# cpu_board.net
KiCad netlist of a schematic drawn in EAGLE
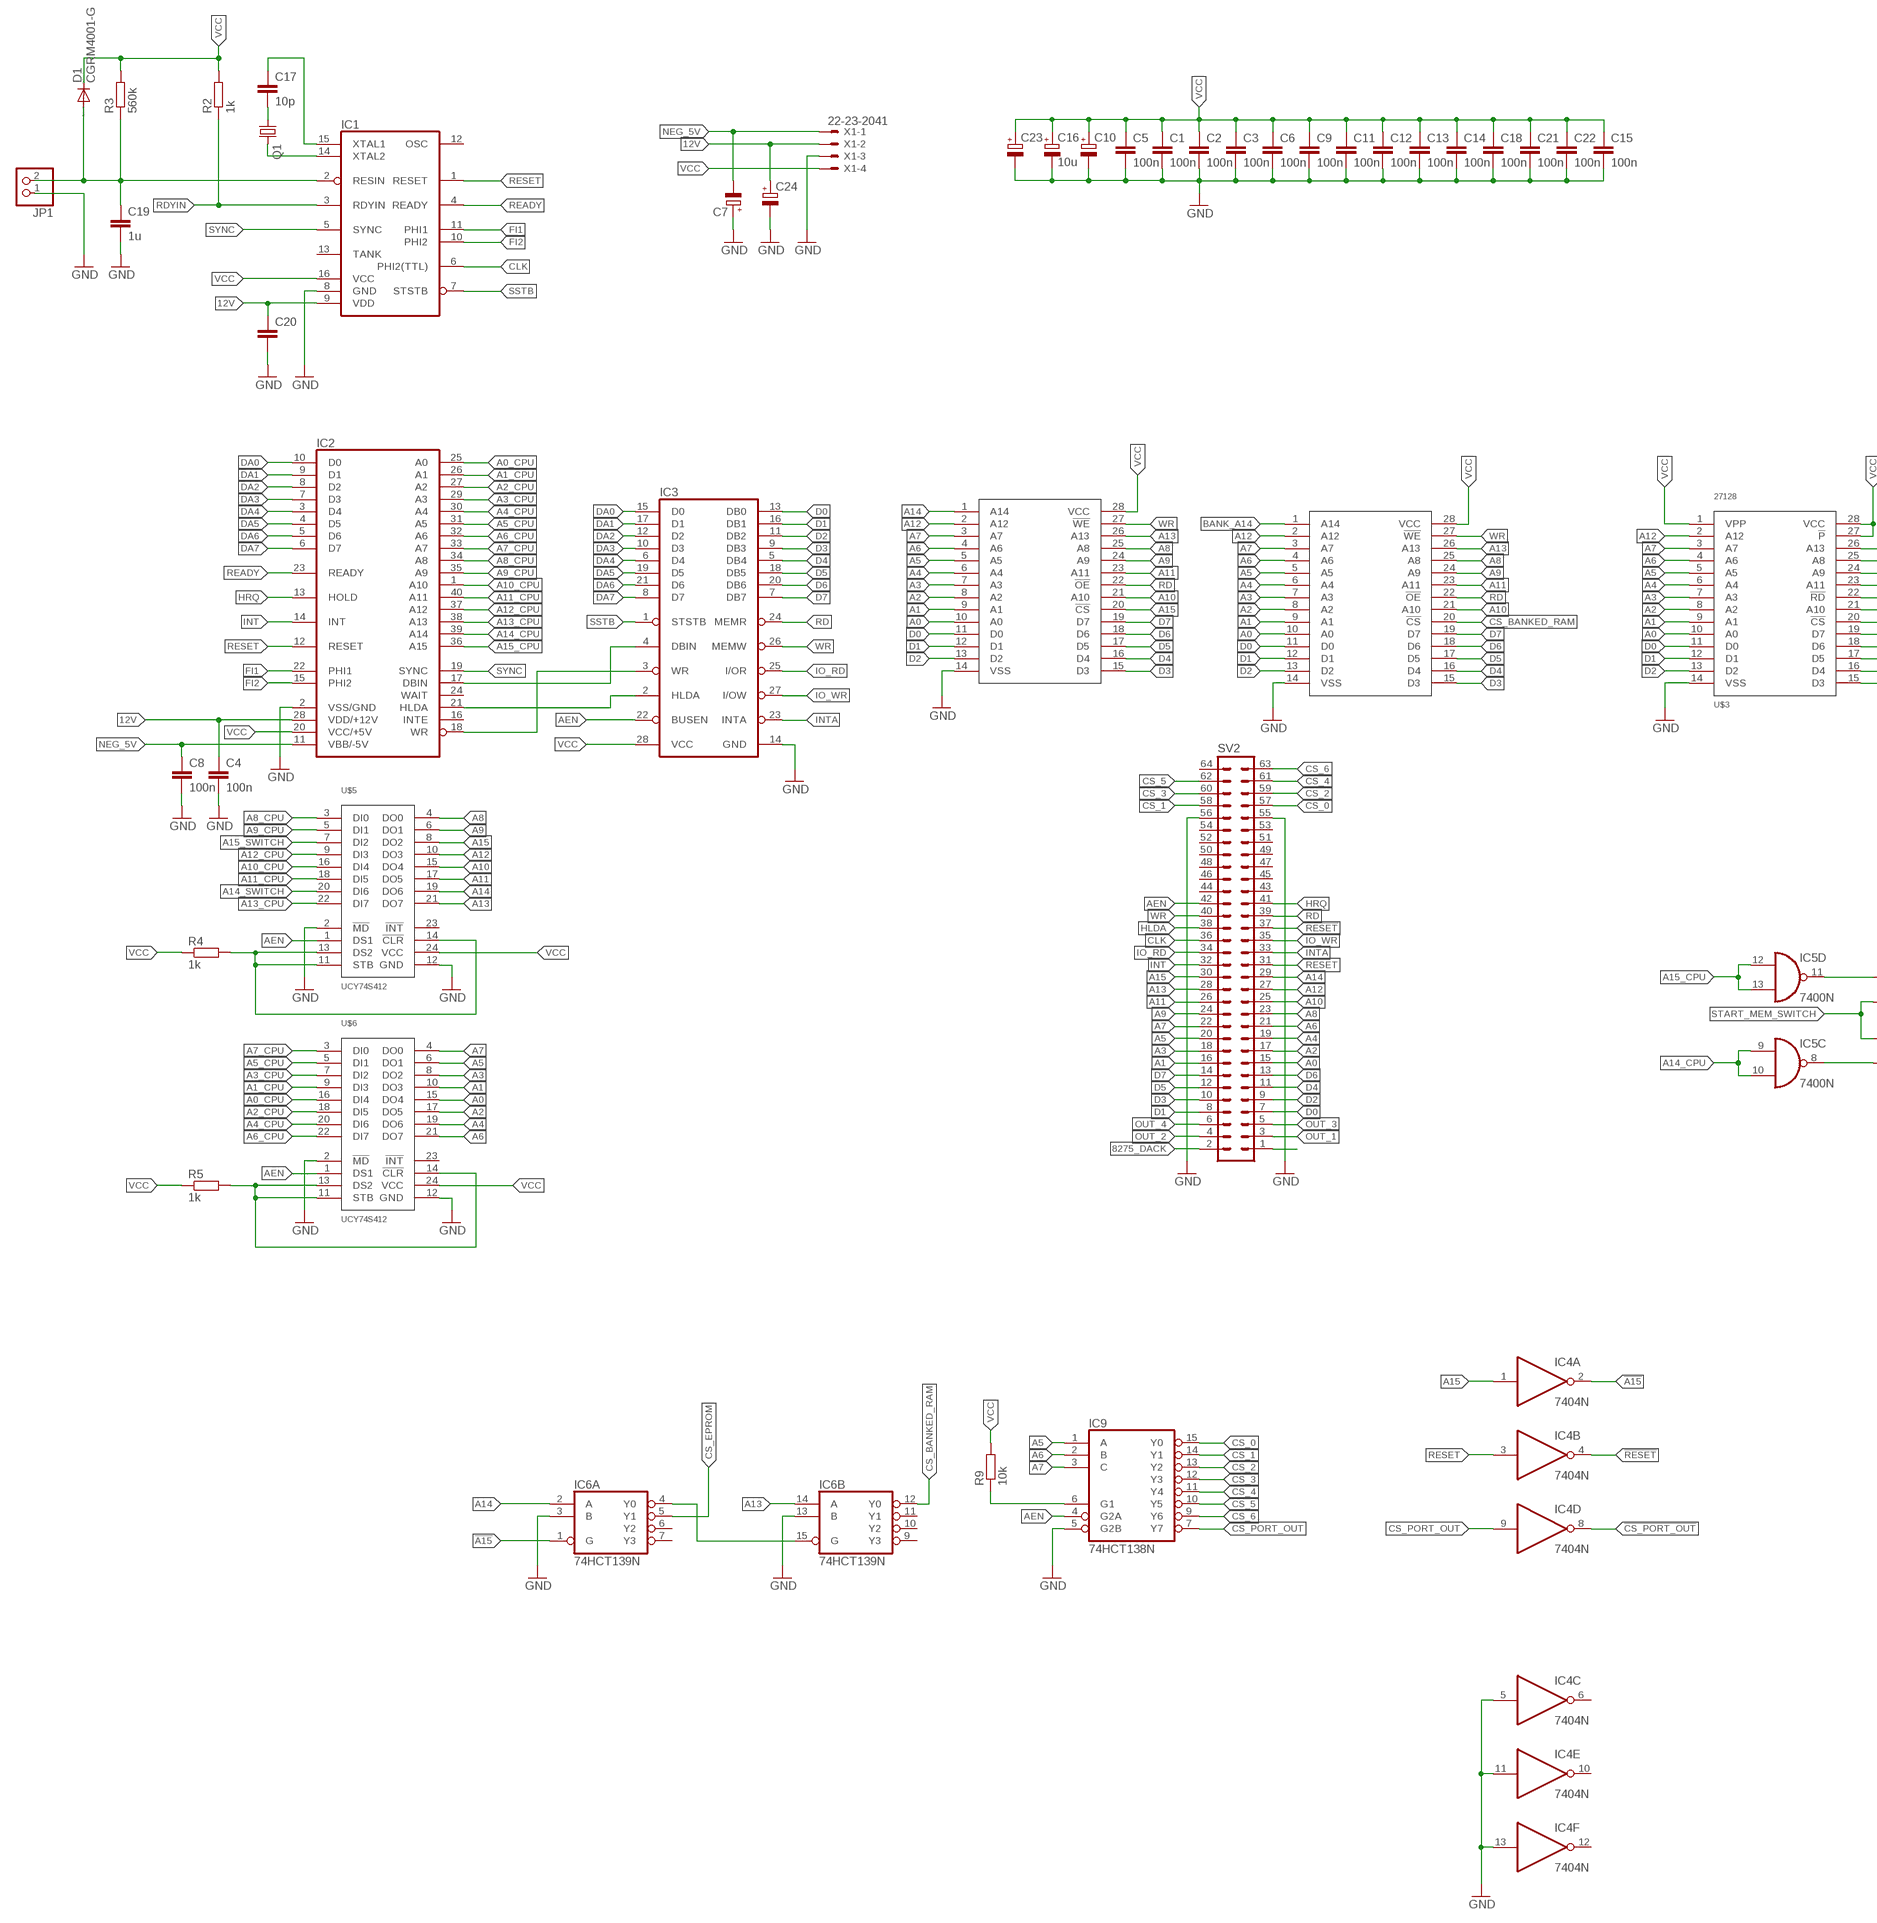
[diagram p0: schematic, sheet 1, part 1 of 2]
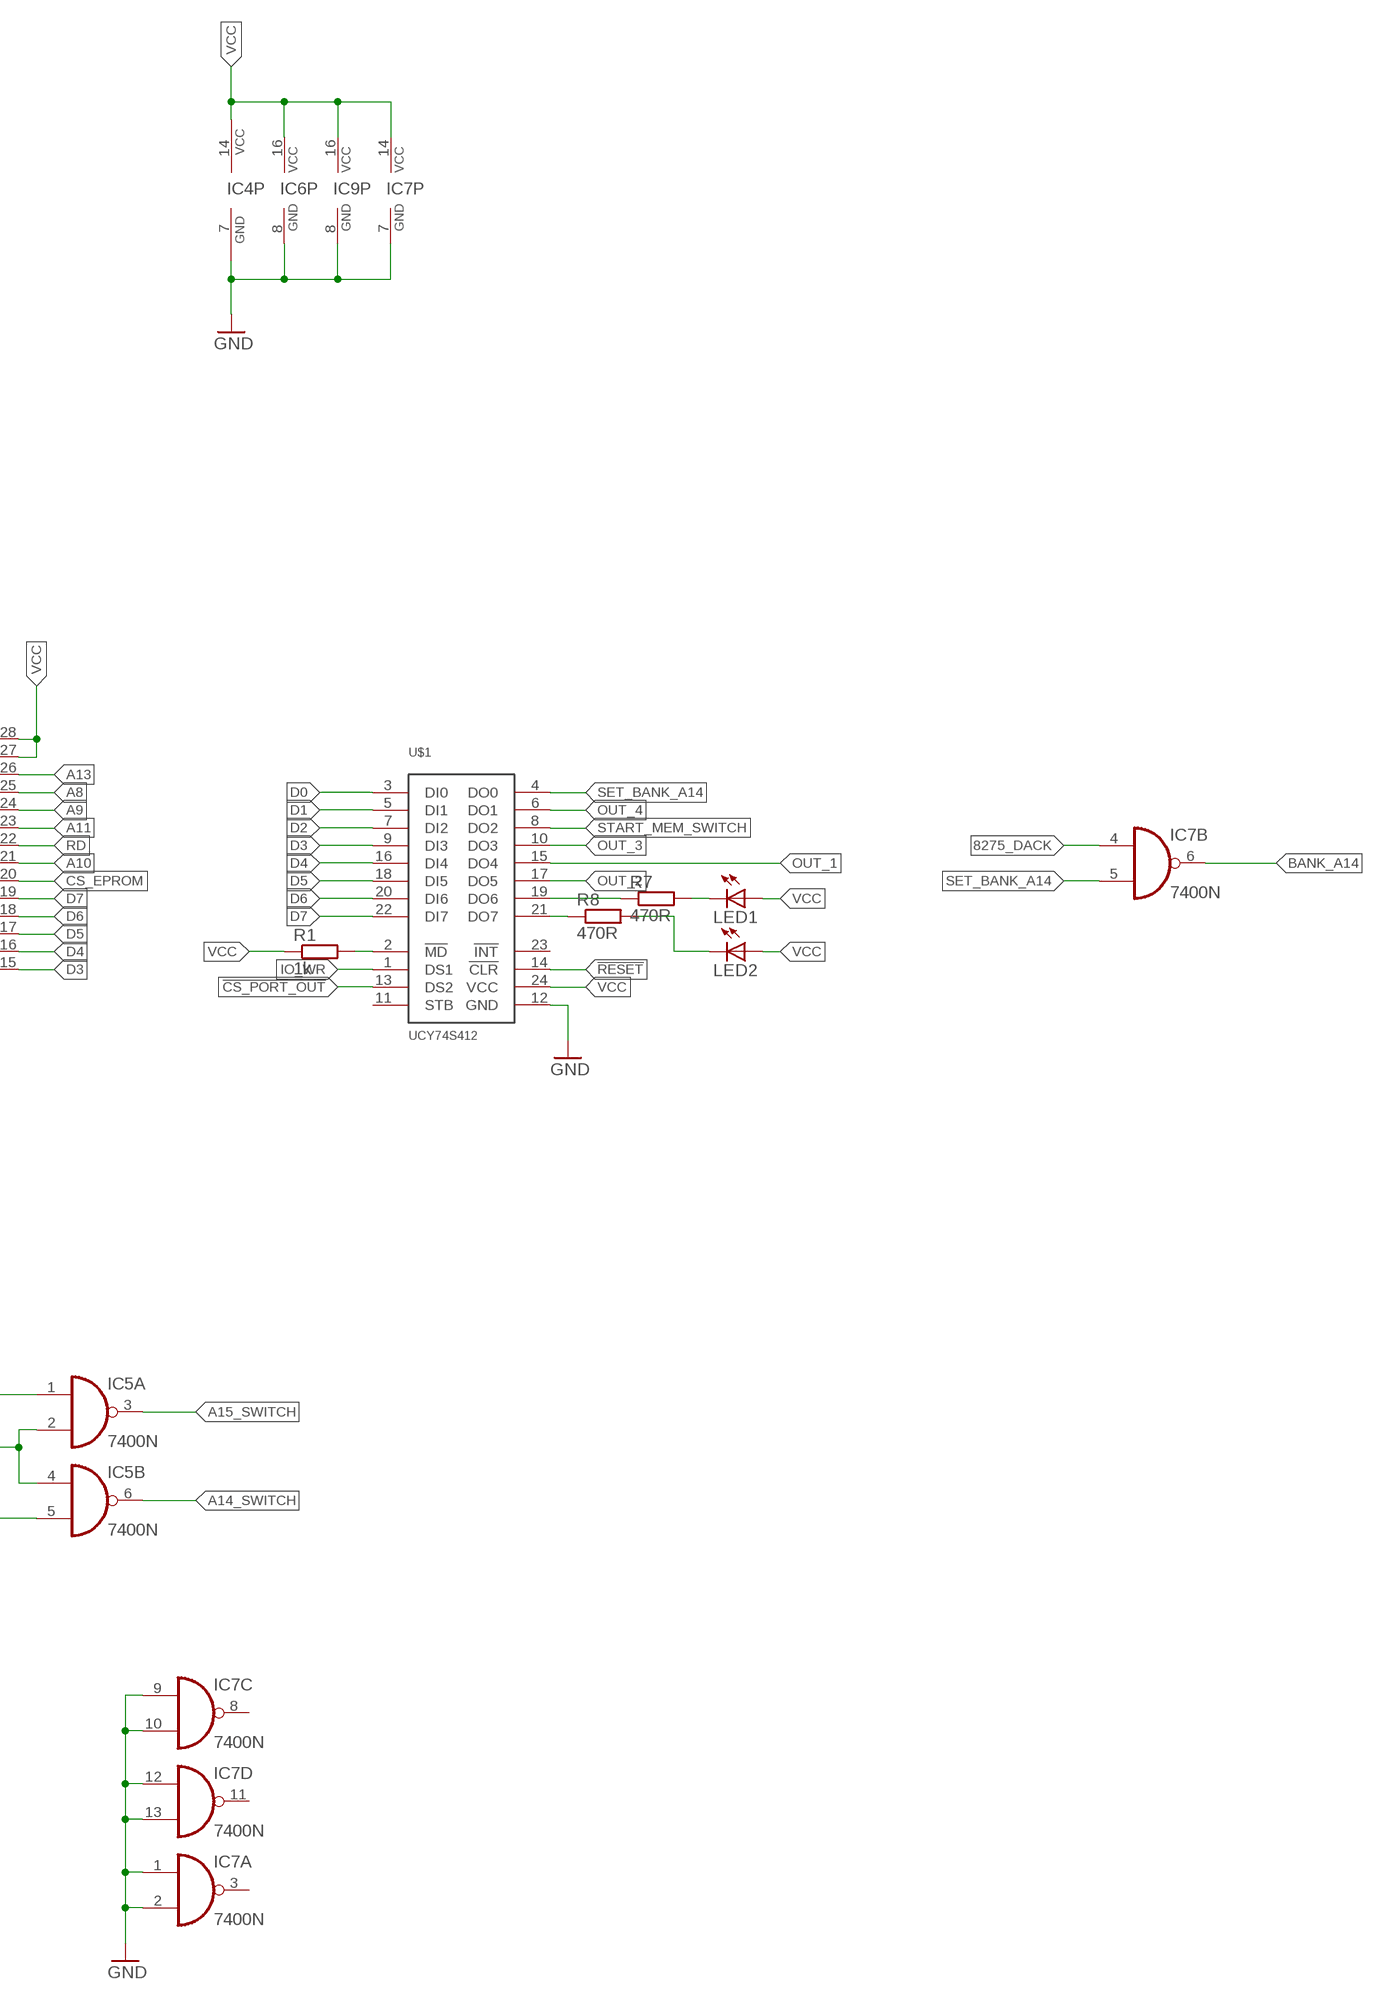
[diagram p1: schematic, sheet 1, part 2 of 2]

(export (version "E")
  (design (tool "Eeschema 10.0.6"))
  (components
    (comp (ref "C1")
      (value "100n")
      (footprint "eagle-import:C1206")
      (libsource (lib "eagle-import") (part "C-EUC1206"))
    )
    (comp (ref "C2")
      (value "100n")
      (footprint "eagle-import:C1206")
      (libsource (lib "eagle-import") (part "C-EUC1206"))
    )
    (comp (ref "C3")
      (value "100n")
      (footprint "eagle-import:C1206")
      (libsource (lib "eagle-import") (part "C-EUC1206"))
    )
    (comp (ref "C4")
      (value "100n")
      (footprint "eagle-import:C1206")
      (libsource (lib "eagle-import") (part "C-EUC1206"))
    )
    (comp (ref "C5")
      (value "100n")
      (footprint "eagle-import:C0603")
      (libsource (lib "eagle-import") (part "C-EUC0603"))
    )
    (comp (ref "C6")
      (value "100n")
      (footprint "eagle-import:C1206")
      (libsource (lib "eagle-import") (part "C-EUC1206"))
    )
    (comp (ref "C7")
      (value "CPOL-EUE2.5-7")
      (footprint "eagle-import:E2,5-7")
      (libsource (lib "eagle-import") (part "CPOL-EUE2.5-7"))
    )
    (comp (ref "C8")
      (value "100n")
      (footprint "eagle-import:C1206")
      (libsource (lib "eagle-import") (part "C-EUC1206"))
    )
    (comp (ref "C9")
      (value "100n")
      (footprint "eagle-import:C1206")
      (libsource (lib "eagle-import") (part "C-EUC1206"))
    )
    (comp (ref "C10")
      (value "CPOL-EUE5-10.5")
      (footprint "eagle-import:E5-10,5")
      (libsource (lib "eagle-import") (part "CPOL-EUE5-10.5"))
    )
    (comp (ref "C11")
      (value "100n")
      (footprint "eagle-import:C0805")
      (libsource (lib "eagle-import") (part "C-EUC0805"))
    )
    (comp (ref "C12")
      (value "100n")
      (footprint "eagle-import:C0805")
      (libsource (lib "eagle-import") (part "C-EUC0805"))
    )
    (comp (ref "C13")
      (value "100n")
      (footprint "eagle-import:C0805")
      (libsource (lib "eagle-import") (part "C-EUC0805"))
    )
    (comp (ref "C14")
      (value "100n")
      (footprint "eagle-import:C1206")
      (libsource (lib "eagle-import") (part "C-EUC1206"))
    )
    (comp (ref "C15")
      (value "100n")
      (footprint "eagle-import:C1206")
      (libsource (lib "eagle-import") (part "C-EUC1206"))
    )
    (comp (ref "C16")
      (value "10u")
      (footprint "eagle-import:SMC_B")
      (libsource (lib "eagle-import") (part "CPOL-EUSMCB"))
    )
    (comp (ref "C17")
      (value "10p")
      (footprint "eagle-import:C0603")
      (libsource (lib "eagle-import") (part "C-EUC0603"))
    )
    (comp (ref "C18")
      (value "100n")
      (footprint "eagle-import:C0603")
      (libsource (lib "eagle-import") (part "C-EUC0603"))
    )
    (comp (ref "C19")
      (value "1u")
      (footprint "eagle-import:C0603")
      (libsource (lib "eagle-import") (part "C-EUC0603"))
    )
    (comp (ref "C20")
      (value "C-EUC0603")
      (footprint "eagle-import:C0603")
      (libsource (lib "eagle-import") (part "C-EUC0603"))
    )
    (comp (ref "C21")
      (value "100n")
      (footprint "eagle-import:C1206")
      (libsource (lib "eagle-import") (part "C-EUC1206"))
    )
    (comp (ref "C22")
      (value "100n")
      (footprint "eagle-import:C0603")
      (libsource (lib "eagle-import") (part "C-EUC0603"))
    )
    (comp (ref "C23")
      (value "CPOL-EUE5-10.5")
      (footprint "eagle-import:E5-10,5")
      (libsource (lib "eagle-import") (part "CPOL-EUE5-10.5"))
    )
    (comp (ref "C24")
      (value "CPOL-EUE3.5-8")
      (footprint "eagle-import:E3,5-8")
      (libsource (lib "eagle-import") (part "CPOL-EUE3.5-8"))
    )
    (comp (ref "D1")
      (value "CGRM4001-G")
      (footprint "eagle-import:SOD-123_MINI-SMA")
      (libsource (lib "eagle-import") (part "CGRM400-G1"))
    )
    (comp (ref "IC1")
      (value "8224")
      (footprint "eagle-import:DIL16")
      (libsource (lib "eagle-import") (part "8224"))
    )
    (comp (ref "IC2")
      (value "8080")
      (footprint "eagle-import:DIL40")
      (libsource (lib "eagle-import") (part "8080"))
    )
    (comp (ref "IC3")
      (value "8228")
      (footprint "eagle-import:DIL28-6")
      (libsource (lib "eagle-import") (part "8228"))
    )
    (comp (ref "IC4")
      (value "7404N")
      (footprint "eagle-import:DIL14")
      (libsource (lib "eagle-import") (part "7404N"))
    )
    (comp (ref "IC5")
      (value "7400N")
      (footprint "eagle-import:DIL14")
      (libsource (lib "eagle-import") (part "7400N"))
    )
    (comp (ref "IC6")
      (value "74HCT139N")
      (footprint "eagle-import:DIL16")
      (libsource (lib "eagle-import") (part "74139NHCT"))
    )
    (comp (ref "IC7")
      (value "7400N")
      (footprint "eagle-import:DIL14")
      (libsource (lib "eagle-import") (part "7400N"))
    )
    (comp (ref "IC9")
      (value "74HCT138N")
      (footprint "eagle-import:DIL16")
      (libsource (lib "eagle-import") (part "74138NHCT"))
    )
    (comp (ref "JP1")
      (value "PINHD-1X2")
      (footprint "eagle-import:1X02")
      (libsource (lib "eagle-import") (part "PINHD-1X2"))
    )
    (comp (ref "LED1")
      (value "LED3MM")
      (footprint "eagle-import:LED3MM")
      (libsource (lib "eagle-import") (part "LED3MM"))
    )
    (comp (ref "LED2")
      (value "LED3MM")
      (footprint "eagle-import:LED3MM")
      (libsource (lib "eagle-import") (part "LED3MM"))
    )
    (comp (ref "Q1")
      (value "CRYSTALHC49U-V")
      (footprint "eagle-import:HC49U-V")
      (libsource (lib "eagle-import") (part "CRYSTALHC49U-V"))
    )
    (comp (ref "R1")
      (value "1k")
      (footprint "eagle-import:M1206")
      (libsource (lib "eagle-import") (part "R-EU_M1206"))
    )
    (comp (ref "R2")
      (value "1k")
      (footprint "eagle-import:R0603")
      (libsource (lib "eagle-import") (part "R-EU_R0603"))
    )
    (comp (ref "R3")
      (value "560k")
      (footprint "eagle-import:R0603")
      (libsource (lib "eagle-import") (part "R-EU_R0603"))
    )
    (comp (ref "R4")
      (value "1k")
      (footprint "eagle-import:R0603")
      (libsource (lib "eagle-import") (part "R-EU_R0603"))
    )
    (comp (ref "R5")
      (value "1k")
      (footprint "eagle-import:0204_7")
      (libsource (lib "eagle-import") (part "R-EU_0204/7"))
    )
    (comp (ref "R7")
      (value "470R")
      (footprint "eagle-import:R0603")
      (libsource (lib "eagle-import") (part "R-EU_R0603"))
    )
    (comp (ref "R8")
      (value "470R")
      (footprint "eagle-import:R0603")
      (libsource (lib "eagle-import") (part "R-EU_R0603"))
    )
    (comp (ref "R9")
      (value "10k")
      (footprint "eagle-import:R0603")
      (libsource (lib "eagle-import") (part "R-EU_R0603"))
    )
    (comp (ref "SV2")
      (value "ML64L")
      (footprint "eagle-import:ML64L")
      (libsource (lib "eagle-import") (part "ML64L"))
    )
    (comp (ref "U$1")
      (value "UCY74S412")
      (footprint "eagle-import:DIL24-6")
      (libsource (lib "eagle-import") (part "UCY74S412"))
    )
    (comp (ref "U$2")
      (value "62256")
      (footprint "eagle-import:DIL28-6")
      (libsource (lib "eagle-import") (part "62256"))
    )
    (comp (ref "U$3")
      (value "27128")
      (footprint "eagle-import:DIL28")
      (libsource (lib "eagle-import") (part "27128"))
    )
    (comp (ref "U$4")
      (value "62256")
      (footprint "eagle-import:DIL28-6")
      (libsource (lib "eagle-import") (part "62256"))
    )
    (comp (ref "U$5")
      (value "UCY74S412")
      (footprint "eagle-import:DIL24-6")
      (libsource (lib "eagle-import") (part "UCY74S412"))
    )
    (comp (ref "U$6")
      (value "UCY74S412")
      (footprint "eagle-import:DIL24-6")
      (libsource (lib "eagle-import") (part "UCY74S412"))
    )
    (comp (ref "X1")
      (value "22-23-2041")
      (footprint "eagle-import:22-23-2041")
      (fields (field (name "MF") "MOLEX"))
      (libsource (lib "eagle-import") (part "22-23-2041"))
    )
  )
  (nets
    (net (code "1") (name "/~{A15}") (class "Default")
      (node (ref "IC4") (pin "2") (pinfunction "O_2") (pintype "output"))
      (node (ref "IC6") (pin "1") (pinfunction "G_1") (pintype "input"))
    )
    (net (code "2") (name "/~{CS_PORT_OUT}") (class "Default")
      (node (ref "IC4") (pin "8") (pinfunction "O_8") (pintype "output"))
      (node (ref "U$1") (pin "13") (pinfunction "DS2_13") (pintype "bidirectional"))
    )
    (net (code "3") (name "/~{RESET}") (class "Default")
      (node (ref "IC4") (pin "4") (pinfunction "O_4") (pintype "output"))
      (node (ref "SV2") (pin "37") (pinfunction "37_37") (pintype "passive"))
      (node (ref "U$1") (pin "14") (pinfunction "~{CLR}_14") (pintype "bidirectional"))
    )
    (net (code "4") (name "12V") (class "Default")
      (node (ref "C20") (pin "1") (pinfunction "1_1") (pintype "passive"))
      (node (ref "C24") (pin "+") (pinfunction "+_+") (pintype "passive"))
      (node (ref "C4") (pin "1") (pinfunction "1_1") (pintype "passive"))
      (node (ref "IC1") (pin "9") (pinfunction "VDD_9") (pintype "power_in"))
      (node (ref "IC2") (pin "28") (pinfunction "VDD/+12V_28") (pintype "power_in"))
      (node (ref "X1") (pin "2") (pinfunction "S_2") (pintype "passive"))
    )
    (net (code "5") (name "8275_DACK") (class "Default")
      (node (ref "IC7") (pin "4") (pinfunction "I0_4") (pintype "input"))
      (node (ref "SV2") (pin "2") (pinfunction "2_2") (pintype "passive"))
    )
    (net (code "6") (name "A0") (class "Default")
      (node (ref "SV2") (pin "15") (pinfunction "15_15") (pintype "passive"))
      (node (ref "U$2") (pin "10") (pinfunction "A0_10") (pintype "bidirectional"))
      (node (ref "U$3") (pin "10") (pinfunction "A0_10") (pintype "bidirectional"))
      (node (ref "U$4") (pin "10") (pinfunction "A0_10") (pintype "bidirectional"))
      (node (ref "U$6") (pin "15") (pinfunction "DO4_15") (pintype "bidirectional"))
    )
    (net (code "7") (name "A0_CPU") (class "Default")
      (node (ref "IC2") (pin "25") (pinfunction "A0_25") (pintype "output"))
      (node (ref "U$6") (pin "16") (pinfunction "DI4_16") (pintype "bidirectional"))
    )
    (net (code "8") (name "A1") (class "Default")
      (node (ref "SV2") (pin "16") (pinfunction "16_16") (pintype "passive"))
      (node (ref "U$2") (pin "9") (pinfunction "A1_9") (pintype "bidirectional"))
      (node (ref "U$3") (pin "9") (pinfunction "A1_9") (pintype "bidirectional"))
      (node (ref "U$4") (pin "9") (pinfunction "A1_9") (pintype "bidirectional"))
      (node (ref "U$6") (pin "10") (pinfunction "DO3_10") (pintype "bidirectional"))
    )
    (net (code "9") (name "A1_CPU") (class "Default")
      (node (ref "IC2") (pin "26") (pinfunction "A1_26") (pintype "output"))
      (node (ref "U$6") (pin "9") (pinfunction "DI3_9") (pintype "bidirectional"))
    )
    (net (code "10") (name "A2") (class "Default")
      (node (ref "SV2") (pin "17") (pinfunction "17_17") (pintype "passive"))
      (node (ref "U$2") (pin "8") (pinfunction "A2_8") (pintype "bidirectional"))
      (node (ref "U$3") (pin "8") (pinfunction "A2_8") (pintype "bidirectional"))
      (node (ref "U$4") (pin "8") (pinfunction "A2_8") (pintype "bidirectional"))
      (node (ref "U$6") (pin "17") (pinfunction "DO5_17") (pintype "bidirectional"))
    )
    (net (code "11") (name "A2_CPU") (class "Default")
      (node (ref "IC2") (pin "27") (pinfunction "A2_27") (pintype "output"))
      (node (ref "U$6") (pin "18") (pinfunction "DI5_18") (pintype "bidirectional"))
    )
    (net (code "12") (name "A3") (class "Default")
      (node (ref "SV2") (pin "18") (pinfunction "18_18") (pintype "passive"))
      (node (ref "U$2") (pin "7") (pinfunction "A3_7") (pintype "bidirectional"))
      (node (ref "U$3") (pin "7") (pinfunction "A3_7") (pintype "bidirectional"))
      (node (ref "U$4") (pin "7") (pinfunction "A3_7") (pintype "bidirectional"))
      (node (ref "U$6") (pin "8") (pinfunction "DO2_8") (pintype "bidirectional"))
    )
    (net (code "13") (name "A3_CPU") (class "Default")
      (node (ref "IC2") (pin "29") (pinfunction "A3_29") (pintype "output"))
      (node (ref "U$6") (pin "7") (pinfunction "DI2_7") (pintype "bidirectional"))
    )
    (net (code "14") (name "A4") (class "Default")
      (node (ref "SV2") (pin "19") (pinfunction "19_19") (pintype "passive"))
      (node (ref "U$2") (pin "6") (pinfunction "A4_6") (pintype "bidirectional"))
      (node (ref "U$3") (pin "6") (pinfunction "A4_6") (pintype "bidirectional"))
      (node (ref "U$4") (pin "6") (pinfunction "A4_6") (pintype "bidirectional"))
      (node (ref "U$6") (pin "19") (pinfunction "DO6_19") (pintype "bidirectional"))
    )
    (net (code "15") (name "A4_CPU") (class "Default")
      (node (ref "IC2") (pin "30") (pinfunction "A4_30") (pintype "output"))
      (node (ref "U$6") (pin "20") (pinfunction "DI6_20") (pintype "bidirectional"))
    )
    (net (code "16") (name "A5") (class "Default")
      (node (ref "IC9") (pin "1") (pinfunction "A_1") (pintype "input"))
      (node (ref "SV2") (pin "20") (pinfunction "20_20") (pintype "passive"))
      (node (ref "U$2") (pin "5") (pinfunction "A5_5") (pintype "bidirectional"))
      (node (ref "U$3") (pin "5") (pinfunction "A5_5") (pintype "bidirectional"))
      (node (ref "U$4") (pin "5") (pinfunction "A5_5") (pintype "bidirectional"))
      (node (ref "U$6") (pin "6") (pinfunction "DO1_6") (pintype "bidirectional"))
    )
    (net (code "17") (name "A5_CPU") (class "Default")
      (node (ref "IC2") (pin "31") (pinfunction "A5_31") (pintype "output"))
      (node (ref "U$6") (pin "5") (pinfunction "DI1_5") (pintype "bidirectional"))
    )
    (net (code "18") (name "A6") (class "Default")
      (node (ref "IC9") (pin "2") (pinfunction "B_2") (pintype "input"))
      (node (ref "SV2") (pin "21") (pinfunction "21_21") (pintype "passive"))
      (node (ref "U$2") (pin "4") (pinfunction "A6_4") (pintype "bidirectional"))
      (node (ref "U$3") (pin "4") (pinfunction "A6_4") (pintype "bidirectional"))
      (node (ref "U$4") (pin "4") (pinfunction "A6_4") (pintype "bidirectional"))
      (node (ref "U$6") (pin "21") (pinfunction "DO7_21") (pintype "bidirectional"))
    )
    (net (code "19") (name "A6_CPU") (class "Default")
      (node (ref "IC2") (pin "32") (pinfunction "A6_32") (pintype "output"))
      (node (ref "U$6") (pin "22") (pinfunction "DI7_22") (pintype "bidirectional"))
    )
    (net (code "20") (name "A7") (class "Default")
      (node (ref "IC9") (pin "3") (pinfunction "C_3") (pintype "input"))
      (node (ref "SV2") (pin "22") (pinfunction "22_22") (pintype "passive"))
      (node (ref "U$2") (pin "3") (pinfunction "A7_3") (pintype "bidirectional"))
      (node (ref "U$3") (pin "3") (pinfunction "A7_3") (pintype "bidirectional"))
      (node (ref "U$4") (pin "3") (pinfunction "A7_3") (pintype "bidirectional"))
      (node (ref "U$6") (pin "4") (pinfunction "DO0_4") (pintype "bidirectional"))
    )
    (net (code "21") (name "A7_CPU") (class "Default")
      (node (ref "IC2") (pin "33") (pinfunction "A7_33") (pintype "output"))
      (node (ref "U$6") (pin "3") (pinfunction "DI0_3") (pintype "bidirectional"))
    )
    (net (code "22") (name "A8") (class "Default")
      (node (ref "SV2") (pin "23") (pinfunction "23_23") (pintype "passive"))
      (node (ref "U$2") (pin "25") (pinfunction "A8_25") (pintype "bidirectional"))
      (node (ref "U$3") (pin "25") (pinfunction "A8_25") (pintype "bidirectional"))
      (node (ref "U$4") (pin "25") (pinfunction "A8_25") (pintype "bidirectional"))
      (node (ref "U$5") (pin "4") (pinfunction "DO0_4") (pintype "bidirectional"))
    )
    (net (code "23") (name "A8_CPU") (class "Default")
      (node (ref "IC2") (pin "34") (pinfunction "A8_34") (pintype "output"))
      (node (ref "U$5") (pin "3") (pinfunction "DI0_3") (pintype "bidirectional"))
    )
    (net (code "24") (name "A9") (class "Default")
      (node (ref "SV2") (pin "24") (pinfunction "24_24") (pintype "passive"))
      (node (ref "U$2") (pin "24") (pinfunction "A9_24") (pintype "bidirectional"))
      (node (ref "U$3") (pin "24") (pinfunction "A9_24") (pintype "bidirectional"))
      (node (ref "U$4") (pin "24") (pinfunction "A9_24") (pintype "bidirectional"))
      (node (ref "U$5") (pin "6") (pinfunction "DO1_6") (pintype "bidirectional"))
    )
    (net (code "25") (name "A9_CPU") (class "Default")
      (node (ref "IC2") (pin "35") (pinfunction "A9_35") (pintype "output"))
      (node (ref "U$5") (pin "5") (pinfunction "DI1_5") (pintype "bidirectional"))
    )
    (net (code "26") (name "A10") (class "Default")
      (node (ref "SV2") (pin "25") (pinfunction "25_25") (pintype "passive"))
      (node (ref "U$2") (pin "21") (pinfunction "A10_21") (pintype "bidirectional"))
      (node (ref "U$3") (pin "21") (pinfunction "A10_21") (pintype "bidirectional"))
      (node (ref "U$4") (pin "21") (pinfunction "A10_21") (pintype "bidirectional"))
      (node (ref "U$5") (pin "15") (pinfunction "DO4_15") (pintype "bidirectional"))
    )
    (net (code "27") (name "A10_CPU") (class "Default")
      (node (ref "IC2") (pin "1") (pinfunction "A10_1") (pintype "output"))
      (node (ref "U$5") (pin "16") (pinfunction "DI4_16") (pintype "bidirectional"))
    )
    (net (code "28") (name "A11") (class "Default")
      (node (ref "SV2") (pin "26") (pinfunction "26_26") (pintype "passive"))
      (node (ref "U$2") (pin "23") (pinfunction "A11_23") (pintype "bidirectional"))
      (node (ref "U$3") (pin "23") (pinfunction "A11_23") (pintype "bidirectional"))
      (node (ref "U$4") (pin "23") (pinfunction "A11_23") (pintype "bidirectional"))
      (node (ref "U$5") (pin "17") (pinfunction "DO5_17") (pintype "bidirectional"))
    )
    (net (code "29") (name "A11_CPU") (class "Default")
      (node (ref "IC2") (pin "40") (pinfunction "A11_40") (pintype "output"))
      (node (ref "U$5") (pin "18") (pinfunction "DI5_18") (pintype "bidirectional"))
    )
    (net (code "30") (name "A12") (class "Default")
      (node (ref "SV2") (pin "27") (pinfunction "27_27") (pintype "passive"))
      (node (ref "U$2") (pin "2") (pinfunction "A12_2") (pintype "bidirectional"))
      (node (ref "U$3") (pin "2") (pinfunction "A12_2") (pintype "bidirectional"))
      (node (ref "U$4") (pin "2") (pinfunction "A12_2") (pintype "bidirectional"))
      (node (ref "U$5") (pin "10") (pinfunction "DO3_10") (pintype "bidirectional"))
    )
    (net (code "31") (name "A12_CPU") (class "Default")
      (node (ref "IC2") (pin "37") (pinfunction "A12_37") (pintype "output"))
      (node (ref "U$5") (pin "9") (pinfunction "DI3_9") (pintype "bidirectional"))
    )
    (net (code "32") (name "A13") (class "Default")
      (node (ref "IC6") (pin "14") (pinfunction "A_14") (pintype "input"))
      (node (ref "SV2") (pin "28") (pinfunction "28_28") (pintype "passive"))
      (node (ref "U$2") (pin "26") (pinfunction "A13_26") (pintype "bidirectional"))
      (node (ref "U$3") (pin "26") (pinfunction "A13_26") (pintype "bidirectional"))
      (node (ref "U$4") (pin "26") (pinfunction "A13_26") (pintype "bidirectional"))
      (node (ref "U$5") (pin "21") (pinfunction "DO7_21") (pintype "bidirectional"))
    )
    (net (code "33") (name "A13_CPU") (class "Default")
      (node (ref "IC2") (pin "38") (pinfunction "A13_38") (pintype "output"))
      (node (ref "U$5") (pin "22") (pinfunction "DI7_22") (pintype "bidirectional"))
    )
    (net (code "34") (name "A14") (class "Default")
      (node (ref "IC6") (pin "2") (pinfunction "A_2") (pintype "input"))
      (node (ref "SV2") (pin "29") (pinfunction "29_29") (pintype "passive"))
      (node (ref "U$4") (pin "1") (pinfunction "A14_1") (pintype "bidirectional"))
      (node (ref "U$5") (pin "19") (pinfunction "DO6_19") (pintype "bidirectional"))
    )
    (net (code "35") (name "A14_CPU") (class "Default")
      (node (ref "IC2") (pin "39") (pinfunction "A14_39") (pintype "output"))
      (node (ref "IC5") (pin "10") (pinfunction "I1_10") (pintype "input"))
      (node (ref "IC5") (pin "9") (pinfunction "I0_9") (pintype "input"))
    )
    (net (code "36") (name "A14_SWITCH") (class "Default")
      (node (ref "IC5") (pin "6") (pinfunction "O_6") (pintype "output"))
      (node (ref "U$5") (pin "20") (pinfunction "DI6_20") (pintype "bidirectional"))
    )
    (net (code "37") (name "A15") (class "Default")
      (node (ref "IC4") (pin "1") (pinfunction "I_1") (pintype "input"))
      (node (ref "SV2") (pin "30") (pinfunction "30_30") (pintype "passive"))
      (node (ref "U$4") (pin "20") (pinfunction "~{CS}_20") (pintype "bidirectional"))
      (node (ref "U$5") (pin "8") (pinfunction "DO2_8") (pintype "bidirectional"))
    )
    (net (code "38") (name "A15_CPU") (class "Default")
      (node (ref "IC2") (pin "36") (pinfunction "A15_36") (pintype "output"))
      (node (ref "IC5") (pin "12") (pinfunction "I0_12") (pintype "input"))
      (node (ref "IC5") (pin "13") (pinfunction "I1_13") (pintype "input"))
    )
    (net (code "39") (name "A15_SWITCH") (class "Default")
      (node (ref "IC5") (pin "3") (pinfunction "O_3") (pintype "output"))
      (node (ref "U$5") (pin "7") (pinfunction "DI2_7") (pintype "bidirectional"))
    )
    (net (code "40") (name "AEN") (class "Default")
      (node (ref "IC3") (pin "22") (pinfunction "BUSEN_22") (pintype "input"))
      (node (ref "IC9") (pin "4") (pinfunction "G2A_4") (pintype "input"))
      (node (ref "SV2") (pin "42") (pinfunction "42_42") (pintype "passive"))
      (node (ref "U$5") (pin "1") (pinfunction "DS1_1") (pintype "bidirectional"))
      (node (ref "U$6") (pin "1") (pinfunction "DS1_1") (pintype "bidirectional"))
    )
    (net (code "41") (name "BANK_A14") (class "Default")
      (node (ref "IC7") (pin "6") (pinfunction "O_6") (pintype "output"))
      (node (ref "U$2") (pin "1") (pinfunction "A14_1") (pintype "bidirectional"))
    )
    (net (code "42") (name "CLK") (class "Default")
      (node (ref "IC1") (pin "6") (pinfunction "PHI2(TTL)_6") (pintype "output"))
      (node (ref "SV2") (pin "36") (pinfunction "36_36") (pintype "passive"))
    )
    (net (code "43") (name "CS_0") (class "Default")
      (node (ref "IC9") (pin "15") (pinfunction "Y0_15") (pintype "output"))
      (node (ref "SV2") (pin "57") (pinfunction "57_57") (pintype "passive"))
    )
    (net (code "44") (name "CS_1") (class "Default")
      (node (ref "IC9") (pin "14") (pinfunction "Y1_14") (pintype "output"))
      (node (ref "SV2") (pin "58") (pinfunction "58_58") (pintype "passive"))
    )
    (net (code "45") (name "CS_2") (class "Default")
      (node (ref "IC9") (pin "13") (pinfunction "Y2_13") (pintype "output"))
      (node (ref "SV2") (pin "59") (pinfunction "59_59") (pintype "passive"))
    )
    (net (code "46") (name "CS_3") (class "Default")
      (node (ref "IC9") (pin "12") (pinfunction "Y3_12") (pintype "output"))
      (node (ref "SV2") (pin "60") (pinfunction "60_60") (pintype "passive"))
    )
    (net (code "47") (name "CS_4") (class "Default")
      (node (ref "IC9") (pin "11") (pinfunction "Y4_11") (pintype "output"))
      (node (ref "SV2") (pin "61") (pinfunction "61_61") (pintype "passive"))
    )
    (net (code "48") (name "CS_5") (class "Default")
      (node (ref "IC9") (pin "10") (pinfunction "Y5_10") (pintype "output"))
      (node (ref "SV2") (pin "62") (pinfunction "62_62") (pintype "passive"))
    )
    (net (code "49") (name "CS_6") (class "Default")
      (node (ref "IC9") (pin "9") (pinfunction "Y6_9") (pintype "output"))
      (node (ref "SV2") (pin "63") (pinfunction "63_63") (pintype "passive"))
    )
    (net (code "50") (name "CS_BANKED_RAM") (class "Default")
      (node (ref "IC6") (pin "12") (pinfunction "Y0_12") (pintype "output"))
      (node (ref "U$2") (pin "20") (pinfunction "~{CS}_20") (pintype "bidirectional"))
    )
    (net (code "51") (name "CS_EPROM") (class "Default")
      (node (ref "IC6") (pin "5") (pinfunction "Y1_5") (pintype "output"))
      (node (ref "U$3") (pin "20") (pinfunction "~{CS}_20") (pintype "bidirectional"))
    )
    (net (code "52") (name "CS_PORT_OUT") (class "Default")
      (node (ref "IC4") (pin "9") (pinfunction "I_9") (pintype "input"))
      (node (ref "IC9") (pin "7") (pinfunction "Y7_7") (pintype "output"))
    )
    (net (code "53") (name "D0") (class "Default")
      (node (ref "IC3") (pin "13") (pinfunction "DB0_13") (pintype "bidirectional"))
      (node (ref "SV2") (pin "7") (pinfunction "7_7") (pintype "passive"))
      (node (ref "U$1") (pin "3") (pinfunction "DI0_3") (pintype "bidirectional"))
      (node (ref "U$2") (pin "11") (pinfunction "D0_11") (pintype "bidirectional"))
      (node (ref "U$3") (pin "11") (pinfunction "D0_11") (pintype "bidirectional"))
      (node (ref "U$4") (pin "11") (pinfunction "D0_11") (pintype "bidirectional"))
    )
    (net (code "54") (name "D1") (class "Default")
      (node (ref "IC3") (pin "16") (pinfunction "DB1_16") (pintype "bidirectional"))
      (node (ref "SV2") (pin "8") (pinfunction "8_8") (pintype "passive"))
      (node (ref "U$1") (pin "5") (pinfunction "DI1_5") (pintype "bidirectional"))
      (node (ref "U$2") (pin "12") (pinfunction "D1_12") (pintype "bidirectional"))
      (node (ref "U$3") (pin "12") (pinfunction "D1_12") (pintype "bidirectional"))
      (node (ref "U$4") (pin "12") (pinfunction "D1_12") (pintype "bidirectional"))
    )
    (net (code "55") (name "D2") (class "Default")
      (node (ref "IC3") (pin "11") (pinfunction "DB2_11") (pintype "bidirectional"))
      (node (ref "SV2") (pin "9") (pinfunction "9_9") (pintype "passive"))
      (node (ref "U$1") (pin "7") (pinfunction "DI2_7") (pintype "bidirectional"))
      (node (ref "U$2") (pin "13") (pinfunction "D2_13") (pintype "bidirectional"))
      (node (ref "U$3") (pin "13") (pinfunction "D2_13") (pintype "bidirectional"))
      (node (ref "U$4") (pin "13") (pinfunction "D2_13") (pintype "bidirectional"))
    )
    (net (code "56") (name "D3") (class "Default")
      (node (ref "IC3") (pin "9") (pinfunction "DB3_9") (pintype "bidirectional"))
      (node (ref "SV2") (pin "10") (pinfunction "10_10") (pintype "passive"))
      (node (ref "U$1") (pin "9") (pinfunction "DI3_9") (pintype "bidirectional"))
      (node (ref "U$2") (pin "15") (pinfunction "D3_15") (pintype "bidirectional"))
      (node (ref "U$3") (pin "15") (pinfunction "D3_15") (pintype "bidirectional"))
      (node (ref "U$4") (pin "15") (pinfunction "D3_15") (pintype "bidirectional"))
    )
    (net (code "57") (name "D4") (class "Default")
      (node (ref "IC3") (pin "5") (pinfunction "DB4_5") (pintype "bidirectional"))
      (node (ref "SV2") (pin "11") (pinfunction "11_11") (pintype "passive"))
      (node (ref "U$1") (pin "16") (pinfunction "DI4_16") (pintype "bidirectional"))
      (node (ref "U$2") (pin "16") (pinfunction "D4_16") (pintype "bidirectional"))
      (node (ref "U$3") (pin "16") (pinfunction "D4_16") (pintype "bidirectional"))
      (node (ref "U$4") (pin "16") (pinfunction "D4_16") (pintype "bidirectional"))
    )
    (net (code "58") (name "D5") (class "Default")
      (node (ref "IC3") (pin "18") (pinfunction "DB5_18") (pintype "bidirectional"))
      (node (ref "SV2") (pin "12") (pinfunction "12_12") (pintype "passive"))
      (node (ref "U$1") (pin "18") (pinfunction "DI5_18") (pintype "bidirectional"))
      (node (ref "U$2") (pin "17") (pinfunction "D5_17") (pintype "bidirectional"))
      (node (ref "U$3") (pin "17") (pinfunction "D5_17") (pintype "bidirectional"))
      (node (ref "U$4") (pin "17") (pinfunction "D5_17") (pintype "bidirectional"))
    )
    (net (code "59") (name "D6") (class "Default")
      (node (ref "IC3") (pin "20") (pinfunction "DB6_20") (pintype "bidirectional"))
      (node (ref "SV2") (pin "13") (pinfunction "13_13") (pintype "passive"))
      (node (ref "U$1") (pin "20") (pinfunction "DI6_20") (pintype "bidirectional"))
      (node (ref "U$2") (pin "18") (pinfunction "D6_18") (pintype "bidirectional"))
      (node (ref "U$3") (pin "18") (pinfunction "D6_18") (pintype "bidirectional"))
      (node (ref "U$4") (pin "18") (pinfunction "D6_18") (pintype "bidirectional"))
    )
    (net (code "60") (name "D7") (class "Default")
      (node (ref "IC3") (pin "7") (pinfunction "DB7_7") (pintype "bidirectional"))
      (node (ref "SV2") (pin "14") (pinfunction "14_14") (pintype "passive"))
      (node (ref "U$1") (pin "22") (pinfunction "DI7_22") (pintype "bidirectional"))
      (node (ref "U$2") (pin "19") (pinfunction "D7_19") (pintype "bidirectional"))
      (node (ref "U$3") (pin "19") (pinfunction "D7_19") (pintype "bidirectional"))
      (node (ref "U$4") (pin "19") (pinfunction "D7_19") (pintype "bidirectional"))
    )
    (net (code "61") (name "DA0") (class "Default")
      (node (ref "IC2") (pin "10") (pinfunction "D0_10") (pintype "bidirectional"))
      (node (ref "IC3") (pin "15") (pinfunction "D0_15") (pintype "bidirectional"))
    )
    (net (code "62") (name "DA1") (class "Default")
      (node (ref "IC2") (pin "9") (pinfunction "D1_9") (pintype "bidirectional"))
      (node (ref "IC3") (pin "17") (pinfunction "D1_17") (pintype "bidirectional"))
    )
    (net (code "63") (name "DA2") (class "Default")
      (node (ref "IC2") (pin "8") (pinfunction "D2_8") (pintype "bidirectional"))
      (node (ref "IC3") (pin "12") (pinfunction "D2_12") (pintype "bidirectional"))
    )
    (net (code "64") (name "DA3") (class "Default")
      (node (ref "IC2") (pin "7") (pinfunction "D3_7") (pintype "bidirectional"))
      (node (ref "IC3") (pin "10") (pinfunction "D3_10") (pintype "bidirectional"))
    )
    (net (code "65") (name "DA4") (class "Default")
      (node (ref "IC2") (pin "3") (pinfunction "D4_3") (pintype "bidirectional"))
      (node (ref "IC3") (pin "6") (pinfunction "D4_6") (pintype "bidirectional"))
    )
    (net (code "66") (name "DA5") (class "Default")
      (node (ref "IC2") (pin "4") (pinfunction "D5_4") (pintype "bidirectional"))
      (node (ref "IC3") (pin "19") (pinfunction "D5_19") (pintype "bidirectional"))
    )
    (net (code "67") (name "DA6") (class "Default")
      (node (ref "IC2") (pin "5") (pinfunction "D6_5") (pintype "bidirectional"))
      (node (ref "IC3") (pin "21") (pinfunction "D6_21") (pintype "bidirectional"))
    )
    (net (code "68") (name "DA7") (class "Default")
      (node (ref "IC2") (pin "6") (pinfunction "D7_6") (pintype "bidirectional"))
      (node (ref "IC3") (pin "8") (pinfunction "D7_8") (pintype "bidirectional"))
    )
    (net (code "69") (name "FI1") (class "Default")
      (node (ref "IC1") (pin "11") (pinfunction "PHI1_11") (pintype "output"))
      (node (ref "IC2") (pin "22") (pinfunction "PHI1_22") (pintype "input"))
    )
    (net (code "70") (name "FI2") (class "Default")
      (node (ref "IC1") (pin "10") (pinfunction "PHI2_10") (pintype "output"))
      (node (ref "IC2") (pin "15") (pinfunction "PHI2_15") (pintype "input"))
    )
    (net (code "71") (name "GND") (class "Default")
      (node (ref "C1") (pin "2") (pinfunction "2_2") (pintype "passive"))
      (node (ref "C10") (pin "-") (pinfunction "-_-") (pintype "passive"))
      (node (ref "C11") (pin "2") (pinfunction "2_2") (pintype "passive"))
      (node (ref "C12") (pin "2") (pinfunction "2_2") (pintype "passive"))
      (node (ref "C13") (pin "2") (pinfunction "2_2") (pintype "passive"))
      (node (ref "C14") (pin "2") (pinfunction "2_2") (pintype "passive"))
      (node (ref "C15") (pin "2") (pinfunction "2_2") (pintype "passive"))
      (node (ref "C16") (pin "-") (pinfunction "-_-") (pintype "passive"))
      (node (ref "C18") (pin "2") (pinfunction "2_2") (pintype "passive"))
      (node (ref "C19") (pin "2") (pinfunction "2_2") (pintype "passive"))
      (node (ref "C2") (pin "2") (pinfunction "2_2") (pintype "passive"))
      (node (ref "C20") (pin "2") (pinfunction "2_2") (pintype "passive"))
      (node (ref "C21") (pin "2") (pinfunction "2_2") (pintype "passive"))
      (node (ref "C22") (pin "2") (pinfunction "2_2") (pintype "passive"))
      (node (ref "C23") (pin "-") (pinfunction "-_-") (pintype "passive"))
      (node (ref "C24") (pin "-") (pinfunction "-_-") (pintype "passive"))
      (node (ref "C3") (pin "2") (pinfunction "2_2") (pintype "passive"))
      (node (ref "C4") (pin "2") (pinfunction "2_2") (pintype "passive"))
      (node (ref "C5") (pin "2") (pinfunction "2_2") (pintype "passive"))
      (node (ref "C6") (pin "2") (pinfunction "2_2") (pintype "passive"))
      (node (ref "C7") (pin "+") (pinfunction "+_+") (pintype "passive"))
      (node (ref "C8") (pin "2") (pinfunction "2_2") (pintype "passive"))
      (node (ref "C9") (pin "2") (pinfunction "2_2") (pintype "passive"))
      (node (ref "IC1") (pin "8") (pinfunction "GND_8") (pintype "power_in"))
      (node (ref "IC2") (pin "2") (pinfunction "VSS/GND_2") (pintype "power_in"))
      (node (ref "IC3") (pin "14") (pinfunction "GND_14") (pintype "power_in"))
      (node (ref "IC4") (pin "11") (pinfunction "I_11") (pintype "input"))
      (node (ref "IC4") (pin "13") (pinfunction "I_13") (pintype "input"))
      (node (ref "IC4") (pin "5") (pinfunction "I_5") (pintype "input"))
      (node (ref "IC4") (pin "7") (pinfunction "GND_7") (pintype "power_in"))
      (node (ref "IC6") (pin "13") (pinfunction "B_13") (pintype "input"))
      (node (ref "IC6") (pin "3") (pinfunction "B_3") (pintype "input"))
      (node (ref "IC6") (pin "8") (pinfunction "GND_8") (pintype "power_in"))
      (node (ref "IC7") (pin "1") (pinfunction "I0_1") (pintype "input"))
      (node (ref "IC7") (pin "10") (pinfunction "I1_10") (pintype "input"))
      (node (ref "IC7") (pin "12") (pinfunction "I0_12") (pintype "input"))
      (node (ref "IC7") (pin "13") (pinfunction "I1_13") (pintype "input"))
      (node (ref "IC7") (pin "2") (pinfunction "I1_2") (pintype "input"))
      (node (ref "IC7") (pin "7") (pinfunction "GND_7") (pintype "power_in"))
      (node (ref "IC7") (pin "9") (pinfunction "I0_9") (pintype "input"))
      (node (ref "IC9") (pin "5") (pinfunction "G2B_5") (pintype "input"))
      (node (ref "IC9") (pin "8") (pinfunction "GND_8") (pintype "power_in"))
      (node (ref "JP1") (pin "1") (pinfunction "1_1") (pintype "passive"))
      (node (ref "SV2") (pin "55") (pinfunction "55_55") (pintype "passive"))
      (node (ref "SV2") (pin "56") (pinfunction "56_56") (pintype "passive"))
      (node (ref "U$1") (pin "12") (pinfunction "GND_12") (pintype "bidirectional"))
      (node (ref "U$2") (pin "14") (pinfunction "VSS_14") (pintype "bidirectional"))
      (node (ref "U$3") (pin "14") (pinfunction "VSS_14") (pintype "bidirectional"))
      (node (ref "U$4") (pin "14") (pinfunction "VSS_14") (pintype "bidirectional"))
      (node (ref "U$5") (pin "12") (pinfunction "GND_12") (pintype "bidirectional"))
      (node (ref "U$5") (pin "2") (pinfunction "~{MD}_2") (pintype "bidirectional"))
      (node (ref "U$6") (pin "12") (pinfunction "GND_12") (pintype "bidirectional"))
      (node (ref "U$6") (pin "2") (pinfunction "~{MD}_2") (pintype "bidirectional"))
      (node (ref "X1") (pin "3") (pinfunction "S_3") (pintype "passive"))
    )
    (net (code "72") (name "HLDA") (class "Default")
      (node (ref "IC2") (pin "21") (pinfunction "HLDA_21") (pintype "output"))
      (node (ref "IC3") (pin "2") (pinfunction "HLDA_2") (pintype "input"))
      (node (ref "SV2") (pin "38") (pinfunction "38_38") (pintype "passive"))
    )
    (net (code "73") (name "HRQ") (class "Default")
      (node (ref "IC2") (pin "13") (pinfunction "HOLD_13") (pintype "input"))
      (node (ref "SV2") (pin "41") (pinfunction "41_41") (pintype "passive"))
    )
    (net (code "74") (name "INT") (class "Default")
      (node (ref "IC2") (pin "14") (pinfunction "INT_14") (pintype "input"))
      (node (ref "SV2") (pin "32") (pinfunction "32_32") (pintype "passive"))
    )
    (net (code "75") (name "INTA") (class "Default")
      (node (ref "IC3") (pin "23") (pinfunction "INTA_23") (pintype "output"))
      (node (ref "SV2") (pin "33") (pinfunction "33_33") (pintype "passive"))
    )
    (net (code "76") (name "IO_RD") (class "Default")
      (node (ref "IC3") (pin "25") (pinfunction "I/OR_25") (pintype "output"))
      (node (ref "SV2") (pin "34") (pinfunction "34_34") (pintype "passive"))
    )
    (net (code "77") (name "IO_WR") (class "Default")
      (node (ref "IC3") (pin "27") (pinfunction "I/OW_27") (pintype "output"))
      (node (ref "SV2") (pin "35") (pinfunction "35_35") (pintype "passive"))
      (node (ref "U$1") (pin "1") (pinfunction "DS1_1") (pintype "bidirectional"))
    )
    (net (code "78") (name "NEG_5V") (class "Default")
      (node (ref "C7") (pin "-") (pinfunction "-_-") (pintype "passive"))
      (node (ref "C8") (pin "1") (pinfunction "1_1") (pintype "passive"))
      (node (ref "IC2") (pin "11") (pinfunction "VBB/-5V_11") (pintype "power_in"))
      (node (ref "X1") (pin "1") (pinfunction "S_1") (pintype "passive"))
    )
    (net (code "79") (name "Net-(C17-Pad2)") (class "Default")
      (node (ref "C17") (pin "2") (pinfunction "2_2") (pintype "passive"))
      (node (ref "Q1") (pin "1") (pinfunction "1_1") (pintype "passive"))
    )
    (net (code "80") (name "Net-(IC1-RESIN)") (class "Default")
      (node (ref "C19") (pin "1") (pinfunction "1_1") (pintype "passive"))
      (node (ref "D1") (pin "A") (pinfunction "A_A") (pintype "passive"))
      (node (ref "IC1") (pin "2") (pinfunction "RESIN_2") (pintype "input"))
      (node (ref "JP1") (pin "2") (pinfunction "2_2") (pintype "passive"))
      (node (ref "R3") (pin "1") (pinfunction "1_1") (pintype "passive"))
    )
    (net (code "81") (name "Net-(IC1-XTAL1)") (class "Default")
      (node (ref "C17") (pin "1") (pinfunction "1_1") (pintype "passive"))
      (node (ref "IC1") (pin "15") (pinfunction "XTAL1_15") (pintype "input"))
    )
    (net (code "82") (name "Net-(IC1-XTAL2)") (class "Default")
      (node (ref "IC1") (pin "14") (pinfunction "XTAL2_14") (pintype "input"))
      (node (ref "Q1") (pin "2") (pinfunction "2_2") (pintype "passive"))
    )
    (net (code "83") (name "Net-(IC2-DBIN)") (class "Default")
      (node (ref "IC2") (pin "17") (pinfunction "DBIN_17") (pintype "output"))
      (node (ref "IC3") (pin "4") (pinfunction "DBIN_4") (pintype "input"))
    )
    (net (code "84") (name "Net-(IC2-WR)") (class "Default")
      (node (ref "IC2") (pin "18") (pinfunction "WR_18") (pintype "output"))
      (node (ref "IC3") (pin "3") (pinfunction "WR_3") (pintype "input"))
    )
    (net (code "85") (name "Net-(IC5A-I0)") (class "Default")
      (node (ref "IC5") (pin "1") (pinfunction "I0_1") (pintype "input"))
      (node (ref "IC5") (pin "11") (pinfunction "O_11") (pintype "output"))
    )
    (net (code "86") (name "Net-(IC5B-I1)") (class "Default")
      (node (ref "IC5") (pin "5") (pinfunction "I1_5") (pintype "input"))
      (node (ref "IC5") (pin "8") (pinfunction "O_8") (pintype "output"))
    )
    (net (code "87") (name "Net-(IC6A-Y0)") (class "Default")
      (node (ref "IC6") (pin "15") (pinfunction "G_15") (pintype "input"))
      (node (ref "IC6") (pin "4") (pinfunction "Y0_4") (pintype "output"))
    )
    (net (code "88") (name "Net-(IC9A-G1)") (class "Default")
      (node (ref "IC9") (pin "6") (pinfunction "G1_6") (pintype "input"))
      (node (ref "R9") (pin "1") (pinfunction "1_1") (pintype "passive"))
    )
    (net (code "89") (name "Net-(LED1-C)") (class "Default")
      (node (ref "LED1") (pin "K") (pinfunction "C_K") (pintype "passive"))
      (node (ref "R7") (pin "2") (pinfunction "2_2") (pintype "passive"))
    )
    (net (code "90") (name "Net-(LED2-C)") (class "Default")
      (node (ref "LED2") (pin "K") (pinfunction "C_K") (pintype "passive"))
      (node (ref "R8") (pin "2") (pinfunction "2_2") (pintype "passive"))
    )
    (net (code "91") (name "Net-(U$1-DO6)") (class "Default")
      (node (ref "R7") (pin "1") (pinfunction "1_1") (pintype "passive"))
      (node (ref "U$1") (pin "19") (pinfunction "DO6_19") (pintype "bidirectional"))
    )
    (net (code "92") (name "Net-(U$1-DO7)") (class "Default")
      (node (ref "R8") (pin "1") (pinfunction "1_1") (pintype "passive"))
      (node (ref "U$1") (pin "21") (pinfunction "DO7_21") (pintype "bidirectional"))
    )
    (net (code "93") (name "Net-(U$1-~{MD})") (class "Default")
      (node (ref "R1") (pin "2") (pinfunction "2_2") (pintype "passive"))
      (node (ref "U$1") (pin "2") (pinfunction "~{MD}_2") (pintype "bidirectional"))
    )
    (net (code "94") (name "Net-(U$5-DS2)") (class "Default")
      (node (ref "R4") (pin "2") (pinfunction "2_2") (pintype "passive"))
      (node (ref "U$5") (pin "11") (pinfunction "STB_11") (pintype "bidirectional"))
      (node (ref "U$5") (pin "13") (pinfunction "DS2_13") (pintype "bidirectional"))
      (node (ref "U$5") (pin "14") (pinfunction "~{CLR}_14") (pintype "bidirectional"))
    )
    (net (code "95") (name "Net-(U$6-DS2)") (class "Default")
      (node (ref "R5") (pin "2") (pinfunction "2_2") (pintype "passive"))
      (node (ref "U$6") (pin "11") (pinfunction "STB_11") (pintype "bidirectional"))
      (node (ref "U$6") (pin "13") (pinfunction "DS2_13") (pintype "bidirectional"))
      (node (ref "U$6") (pin "14") (pinfunction "~{CLR}_14") (pintype "bidirectional"))
    )
    (net (code "96") (name "OUT_1") (class "Default")
      (node (ref "SV2") (pin "3") (pinfunction "3_3") (pintype "passive"))
      (node (ref "U$1") (pin "15") (pinfunction "DO4_15") (pintype "bidirectional"))
    )
    (net (code "97") (name "OUT_2") (class "Default")
      (node (ref "SV2") (pin "4") (pinfunction "4_4") (pintype "passive"))
      (node (ref "U$1") (pin "17") (pinfunction "DO5_17") (pintype "bidirectional"))
    )
    (net (code "98") (name "OUT_3") (class "Default")
      (node (ref "SV2") (pin "5") (pinfunction "5_5") (pintype "passive"))
      (node (ref "U$1") (pin "10") (pinfunction "DO3_10") (pintype "bidirectional"))
    )
    (net (code "99") (name "OUT_4") (class "Default")
      (node (ref "SV2") (pin "6") (pinfunction "6_6") (pintype "passive"))
      (node (ref "U$1") (pin "6") (pinfunction "DO1_6") (pintype "bidirectional"))
    )
    (net (code "100") (name "RD") (class "Default")
      (node (ref "IC3") (pin "24") (pinfunction "MEMR_24") (pintype "output"))
      (node (ref "SV2") (pin "39") (pinfunction "39_39") (pintype "passive"))
      (node (ref "U$2") (pin "22") (pinfunction "~{OE}_22") (pintype "bidirectional"))
      (node (ref "U$3") (pin "22") (pinfunction "~{RD}_22") (pintype "bidirectional"))
      (node (ref "U$4") (pin "22") (pinfunction "~{OE}_22") (pintype "bidirectional"))
    )
    (net (code "101") (name "RDYIN") (class "Default")
      (node (ref "IC1") (pin "3") (pinfunction "RDYIN_3") (pintype "input"))
      (node (ref "R2") (pin "1") (pinfunction "1_1") (pintype "passive"))
      (node (ref "SV2") (pin "1") (pinfunction "1_1") (pintype "passive"))
    )
    (net (code "102") (name "READY") (class "Default")
      (node (ref "IC1") (pin "4") (pinfunction "READY_4") (pintype "output"))
      (node (ref "IC2") (pin "23") (pinfunction "READY_23") (pintype "input"))
    )
    (net (code "103") (name "RESET") (class "Default")
      (node (ref "IC1") (pin "1") (pinfunction "RESET_1") (pintype "output"))
      (node (ref "IC2") (pin "12") (pinfunction "RESET_12") (pintype "input"))
      (node (ref "IC4") (pin "3") (pinfunction "I_3") (pintype "input"))
      (node (ref "SV2") (pin "31") (pinfunction "31_31") (pintype "passive"))
    )
    (net (code "104") (name "SET_BANK_A14") (class "Default")
      (node (ref "IC7") (pin "5") (pinfunction "I1_5") (pintype "input"))
      (node (ref "U$1") (pin "4") (pinfunction "DO0_4") (pintype "bidirectional"))
    )
    (net (code "105") (name "SSTB") (class "Default")
      (node (ref "IC1") (pin "7") (pinfunction "STSTB_7") (pintype "output"))
      (node (ref "IC3") (pin "1") (pinfunction "STSTB_1") (pintype "input"))
    )
    (net (code "106") (name "START_MEM_SWITCH") (class "Default")
      (node (ref "IC5") (pin "2") (pinfunction "I1_2") (pintype "input"))
      (node (ref "IC5") (pin "4") (pinfunction "I0_4") (pintype "input"))
      (node (ref "U$1") (pin "8") (pinfunction "DO2_8") (pintype "bidirectional"))
    )
    (net (code "107") (name "SYNC") (class "Default")
      (node (ref "IC1") (pin "5") (pinfunction "SYNC_5") (pintype "input"))
      (node (ref "IC2") (pin "19") (pinfunction "SYNC_19") (pintype "output"))
    )
    (net (code "108") (name "VCC") (class "Default")
      (node (ref "C1") (pin "1") (pinfunction "1_1") (pintype "passive"))
      (node (ref "C10") (pin "+") (pinfunction "+_+") (pintype "passive"))
      (node (ref "C11") (pin "1") (pinfunction "1_1") (pintype "passive"))
      (node (ref "C12") (pin "1") (pinfunction "1_1") (pintype "passive"))
      (node (ref "C13") (pin "1") (pinfunction "1_1") (pintype "passive"))
      (node (ref "C14") (pin "1") (pinfunction "1_1") (pintype "passive"))
      (node (ref "C15") (pin "1") (pinfunction "1_1") (pintype "passive"))
      (node (ref "C16") (pin "+") (pinfunction "+_+") (pintype "passive"))
      (node (ref "C18") (pin "1") (pinfunction "1_1") (pintype "passive"))
      (node (ref "C2") (pin "1") (pinfunction "1_1") (pintype "passive"))
      (node (ref "C21") (pin "1") (pinfunction "1_1") (pintype "passive"))
      (node (ref "C22") (pin "1") (pinfunction "1_1") (pintype "passive"))
      (node (ref "C23") (pin "+") (pinfunction "+_+") (pintype "passive"))
      (node (ref "C3") (pin "1") (pinfunction "1_1") (pintype "passive"))
      (node (ref "C5") (pin "1") (pinfunction "1_1") (pintype "passive"))
      (node (ref "C6") (pin "1") (pinfunction "1_1") (pintype "passive"))
      (node (ref "C9") (pin "1") (pinfunction "1_1") (pintype "passive"))
      (node (ref "D1") (pin "C") (pinfunction "C_C") (pintype "passive"))
      (node (ref "IC1") (pin "16") (pinfunction "VCC_16") (pintype "power_in"))
      (node (ref "IC2") (pin "20") (pinfunction "VCC/+5V_20") (pintype "power_in"))
      (node (ref "IC3") (pin "28") (pinfunction "VCC_28") (pintype "power_in"))
      (node (ref "IC4") (pin "14") (pinfunction "VCC_14") (pintype "power_in"))
      (node (ref "IC6") (pin "16") (pinfunction "VCC_16") (pintype "power_in"))
      (node (ref "IC7") (pin "14") (pinfunction "VCC_14") (pintype "power_in"))
      (node (ref "IC9") (pin "16") (pinfunction "VCC_16") (pintype "power_in"))
      (node (ref "LED1") (pin "A") (pinfunction "A_A") (pintype "passive"))
      (node (ref "LED2") (pin "A") (pinfunction "A_A") (pintype "passive"))
      (node (ref "R1") (pin "1") (pinfunction "1_1") (pintype "passive"))
      (node (ref "R2") (pin "2") (pinfunction "2_2") (pintype "passive"))
      (node (ref "R3") (pin "2") (pinfunction "2_2") (pintype "passive"))
      (node (ref "R4") (pin "1") (pinfunction "1_1") (pintype "passive"))
      (node (ref "R5") (pin "1") (pinfunction "1_1") (pintype "passive"))
      (node (ref "R9") (pin "2") (pinfunction "2_2") (pintype "passive"))
      (node (ref "U$1") (pin "24") (pinfunction "VCC_24") (pintype "bidirectional"))
      (node (ref "U$2") (pin "28") (pinfunction "VCC_28") (pintype "bidirectional"))
      (node (ref "U$3") (pin "1") (pinfunction "VPP_1") (pintype "bidirectional"))
      (node (ref "U$3") (pin "27") (pinfunction "~{P}_27") (pintype "bidirectional"))
      (node (ref "U$3") (pin "28") (pinfunction "VCC_28") (pintype "bidirectional"))
      (node (ref "U$4") (pin "28") (pinfunction "VCC_28") (pintype "bidirectional"))
      (node (ref "U$5") (pin "24") (pinfunction "VCC_24") (pintype "bidirectional"))
      (node (ref "U$6") (pin "24") (pinfunction "VCC_24") (pintype "bidirectional"))
      (node (ref "X1") (pin "4") (pinfunction "S_4") (pintype "passive"))
    )
    (net (code "109") (name "WR") (class "Default")
      (node (ref "IC3") (pin "26") (pinfunction "MEMW_26") (pintype "output"))
      (node (ref "SV2") (pin "40") (pinfunction "40_40") (pintype "passive"))
      (node (ref "U$2") (pin "27") (pinfunction "~{WE}_27") (pintype "bidirectional"))
      (node (ref "U$4") (pin "27") (pinfunction "~{WE}_27") (pintype "bidirectional"))
    )
    (net (code "110") (name "unconnected-(IC1-OSC-Pad12)") (class "Default")
      (node (ref "IC1") (pin "12") (pinfunction "OSC_12") (pintype "output"))
    )
    (net (code "111") (name "unconnected-(IC1-TANK-Pad13)") (class "Default")
      (node (ref "IC1") (pin "13") (pinfunction "TANK_13") (pintype "input"))
    )
    (net (code "112") (name "unconnected-(IC2-INTE-Pad16)") (class "Default")
      (node (ref "IC2") (pin "16") (pinfunction "INTE_16") (pintype "output"))
    )
    (net (code "113") (name "unconnected-(IC2-WAIT-Pad24)") (class "Default")
      (node (ref "IC2") (pin "24") (pinfunction "WAIT_24") (pintype "output"))
    )
    (net (code "114") (name "unconnected-(IC4C-O-Pad6)") (class "Default")
      (node (ref "IC4") (pin "6") (pinfunction "O_6") (pintype "output"))
    )
    (net (code "115") (name "unconnected-(IC4E-O-Pad10)") (class "Default")
      (node (ref "IC4") (pin "10") (pinfunction "O_10") (pintype "output"))
    )
    (net (code "116") (name "unconnected-(IC4F-O-Pad12)") (class "Default")
      (node (ref "IC4") (pin "12") (pinfunction "O_12") (pintype "output"))
    )
    (net (code "117") (name "unconnected-(IC6A-Y2-Pad6)") (class "Default")
      (node (ref "IC6") (pin "6") (pinfunction "Y2_6") (pintype "output"))
    )
    (net (code "118") (name "unconnected-(IC6A-Y3-Pad7)") (class "Default")
      (node (ref "IC6") (pin "7") (pinfunction "Y3_7") (pintype "output"))
    )
    (net (code "119") (name "unconnected-(IC6B-Y1-Pad11)") (class "Default")
      (node (ref "IC6") (pin "11") (pinfunction "Y1_11") (pintype "output"))
    )
    (net (code "120") (name "unconnected-(IC6B-Y2-Pad10)") (class "Default")
      (node (ref "IC6") (pin "10") (pinfunction "Y2_10") (pintype "output"))
    )
    (net (code "121") (name "unconnected-(IC6B-Y3-Pad9)") (class "Default")
      (node (ref "IC6") (pin "9") (pinfunction "Y3_9") (pintype "output"))
    )
    (net (code "122") (name "unconnected-(IC7A-O-Pad3)") (class "Default")
      (node (ref "IC7") (pin "3") (pinfunction "O_3") (pintype "output"))
    )
    (net (code "123") (name "unconnected-(IC7C-O-Pad8)") (class "Default")
      (node (ref "IC7") (pin "8") (pinfunction "O_8") (pintype "output"))
    )
    (net (code "124") (name "unconnected-(IC7D-O-Pad11)") (class "Default")
      (node (ref "IC7") (pin "11") (pinfunction "O_11") (pintype "output"))
    )
    (net (code "125") (name "unconnected-(SV2-Pad43)") (class "Default")
      (node (ref "SV2") (pin "43") (pinfunction "43_43") (pintype "passive"))
    )
    (net (code "126") (name "unconnected-(SV2-Pad44)") (class "Default")
      (node (ref "SV2") (pin "44") (pinfunction "44_44") (pintype "passive"))
    )
    (net (code "127") (name "unconnected-(SV2-Pad45)") (class "Default")
      (node (ref "SV2") (pin "45") (pinfunction "45_45") (pintype "passive"))
    )
    (net (code "128") (name "unconnected-(SV2-Pad46)") (class "Default")
      (node (ref "SV2") (pin "46") (pinfunction "46_46") (pintype "passive"))
    )
    (net (code "129") (name "unconnected-(SV2-Pad47)") (class "Default")
      (node (ref "SV2") (pin "47") (pinfunction "47_47") (pintype "passive"))
    )
    (net (code "130") (name "unconnected-(SV2-Pad48)") (class "Default")
      (node (ref "SV2") (pin "48") (pinfunction "48_48") (pintype "passive"))
    )
    (net (code "131") (name "unconnected-(SV2-Pad49)") (class "Default")
      (node (ref "SV2") (pin "49") (pinfunction "49_49") (pintype "passive"))
    )
    (net (code "132") (name "unconnected-(SV2-Pad50)") (class "Default")
      (node (ref "SV2") (pin "50") (pinfunction "50_50") (pintype "passive"))
    )
    (net (code "133") (name "unconnected-(SV2-Pad51)") (class "Default")
      (node (ref "SV2") (pin "51") (pinfunction "51_51") (pintype "passive"))
    )
    (net (code "134") (name "unconnected-(SV2-Pad52)") (class "Default")
      (node (ref "SV2") (pin "52") (pinfunction "52_52") (pintype "passive"))
    )
    (net (code "135") (name "unconnected-(SV2-Pad53)") (class "Default")
      (node (ref "SV2") (pin "53") (pinfunction "53_53") (pintype "passive"))
    )
    (net (code "136") (name "unconnected-(SV2-Pad54)") (class "Default")
      (node (ref "SV2") (pin "54") (pinfunction "54_54") (pintype "passive"))
    )
    (net (code "137") (name "unconnected-(SV2-Pad64)") (class "Default")
      (node (ref "SV2") (pin "64") (pinfunction "64_64") (pintype "passive"))
    )
    (net (code "138") (name "unconnected-(U$1-STB-Pad11)") (class "Default")
      (node (ref "U$1") (pin "11") (pinfunction "STB_11") (pintype "bidirectional"))
    )
    (net (code "139") (name "unconnected-(U$1-~{INT}-Pad23)") (class "Default")
      (node (ref "U$1") (pin "23") (pinfunction "~{INT}_23") (pintype "bidirectional"))
    )
    (net (code "140") (name "unconnected-(U$5-~{INT}-Pad23)") (class "Default")
      (node (ref "U$5") (pin "23") (pinfunction "~{INT}_23") (pintype "bidirectional"))
    )
    (net (code "141") (name "unconnected-(U$6-~{INT}-Pad23)") (class "Default")
      (node (ref "U$6") (pin "23") (pinfunction "~{INT}_23") (pintype "bidirectional"))
    )
  )
)
